# khanh_PB_ip5306_1_0.net
KiCad netlist of a schematic drawn in EAGLE
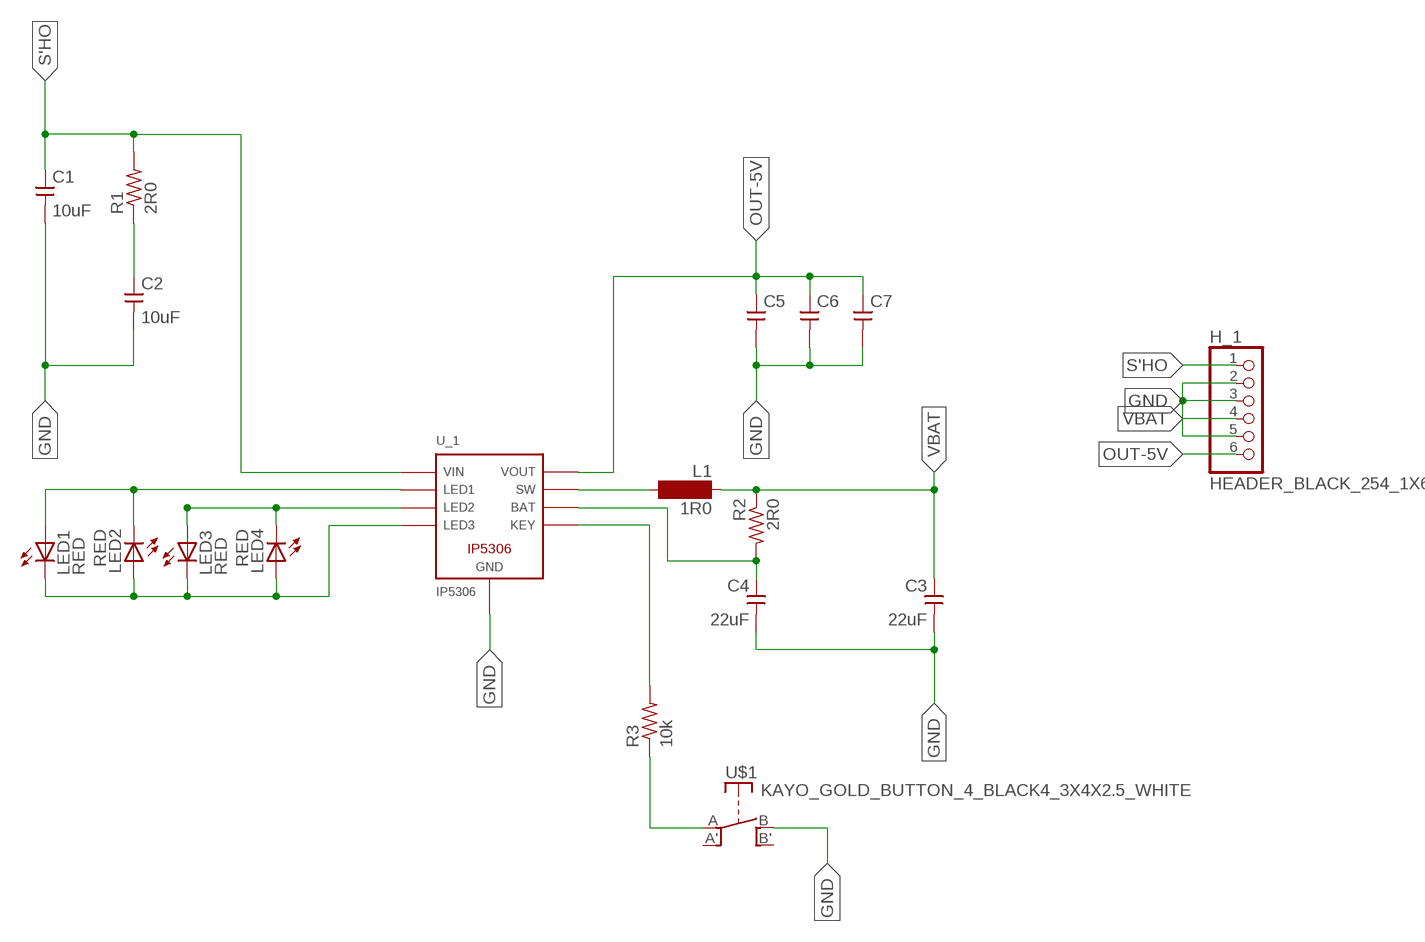
[diagram p0: schematic, sheet 1]

(export (version "E")
  (design (tool "Eeschema 10.0.6"))
  (components
    (comp (ref "C1")
      (value "10uF")
      (footprint "eagle-import:C1206")
      (libsource (lib "eagle-import") (part "KAYO_CAP_CERAMIC_120610UF"))
    )
    (comp (ref "C2")
      (value "10uF")
      (footprint "eagle-import:C1206")
      (libsource (lib "eagle-import") (part "KAYO_CAP_CERAMIC_120610UF"))
    )
    (comp (ref "C3")
      (value "22uF")
      (footprint "eagle-import:C1206")
      (libsource (lib "eagle-import") (part "KAYO_CAP_CERAMIC_120622UF"))
    )
    (comp (ref "C4")
      (value "22uF")
      (footprint "eagle-import:C1206")
      (libsource (lib "eagle-import") (part "KAYO_CAP_CERAMIC_120622UF"))
    )
    (comp (ref "C5")
      (value "KAYO_CAP_CERAMIC22UF_KXN_0603")
      (footprint "eagle-import:KXN_C0603")
      (libsource (lib "eagle-import") (part "KAYO_CAP_CERAMIC_KXN_060322UF"))
    )
    (comp (ref "C6")
      (value "KAYO_CAP_CERAMIC22UF_KXN_0603")
      (footprint "eagle-import:KXN_C0603")
      (libsource (lib "eagle-import") (part "KAYO_CAP_CERAMIC_KXN_060322UF"))
    )
    (comp (ref "C7")
      (value "KAYO_CAP_CERAMIC22UF_KXN_0603")
      (footprint "eagle-import:KXN_C0603")
      (libsource (lib "eagle-import") (part "KAYO_CAP_CERAMIC_KXN_060322UF"))
    )
    (comp (ref "H_1")
      (value "HEADER_BLACK_254_1X6")
      (footprint "eagle-import:HEADER_1X6_254")
      (libsource (lib "eagle-import") (part "KXN_HEADER_1X6"))
    )
    (comp (ref "L1")
      (value "1R0")
      (footprint "eagle-import:CKST_0603_0630_PACK")
      (libsource (lib "eagle-import") (part "INDUCTOR_FEEDER_KAYO_0650"))
    )
    (comp (ref "LED1")
      (value "RED")
      (footprint "eagle-import:KXN_LED_0603")
      (libsource (lib "eagle-import") (part "KAYO_LED_KXN_LED_0603_RED"))
    )
    (comp (ref "LED2")
      (value "RED")
      (footprint "eagle-import:KXN_LED_0603")
      (libsource (lib "eagle-import") (part "KAYO_LED_KXN_LED_0603_RED"))
    )
    (comp (ref "LED3")
      (value "RED")
      (footprint "eagle-import:KXN_LED_0603")
      (libsource (lib "eagle-import") (part "KAYO_LED_KXN_LED_0603_RED"))
    )
    (comp (ref "LED4")
      (value "RED")
      (footprint "eagle-import:KXN_LED_0603")
      (libsource (lib "eagle-import") (part "KAYO_LED_KXN_LED_0603_RED"))
    )
    (comp (ref "R1")
      (value "2R0")
      (footprint "eagle-import:R0603")
      (libsource (lib "eagle-import") (part "R-US_R0603"))
    )
    (comp (ref "R2")
      (value "2R0")
      (footprint "eagle-import:R0603")
      (libsource (lib "eagle-import") (part "R-US_R0603"))
    )
    (comp (ref "R3")
      (value "10k")
      (footprint "eagle-import:R0603")
      (libsource (lib "eagle-import") (part "R-US_R0603"))
    )
    (comp (ref "U$1")
      (value "KAYO_GOLD_BUTTON_4_BLACK4_3X4X2.5_WHITE")
      (footprint "eagle-import:KXN_BUTTON_3_4_2.5MM")
      (libsource (lib "eagle-import") (part "KAYO_GOLD_BUTTON_44_3X4X2.5_WHITE_BLACK"))
    )
    (comp (ref "U_1")
      (value "IP5306")
      (footprint "eagle-import:ESOP8")
      (libsource (lib "eagle-import") (part "IP5306_1"))
    )
  )
  (nets
    (net (code "1") (name "GND") (class "Default")
      (node (ref "C1") (pin "2") (pinfunction "-_2") (pintype "passive"))
      (node (ref "C2") (pin "2") (pinfunction "-_2") (pintype "passive"))
      (node (ref "C3") (pin "2") (pinfunction "-_2") (pintype "passive"))
      (node (ref "C4") (pin "2") (pinfunction "-_2") (pintype "passive"))
      (node (ref "C5") (pin "2") (pinfunction "-_2") (pintype "passive"))
      (node (ref "C6") (pin "2") (pinfunction "-_2") (pintype "passive"))
      (node (ref "C7") (pin "2") (pinfunction "-_2") (pintype "passive"))
      (node (ref "H_1") (pin "2") (pinfunction "2_2") (pintype "passive"))
      (node (ref "H_1") (pin "3") (pinfunction "3_3") (pintype "passive"))
      (node (ref "H_1") (pin "5") (pinfunction "5_5") (pintype "passive"))
      (node (ref "U$1") (pin "B") (pinfunction "B_B") (pintype "passive"))
      (node (ref "U_1") (pin "9") (pinfunction "P$9_9") (pintype "power_in"))
    )
    (net (code "2") (name "Net-(C2-+)") (class "Default")
      (node (ref "C2") (pin "1") (pinfunction "+_1") (pintype "passive"))
      (node (ref "R1") (pin "1") (pinfunction "1_1") (pintype "passive"))
    )
    (net (code "3") (name "Net-(C4-+)") (class "Default")
      (node (ref "C4") (pin "1") (pinfunction "+_1") (pintype "passive"))
      (node (ref "R2") (pin "2") (pinfunction "2_2") (pintype "passive"))
      (node (ref "U_1") (pin "6") (pinfunction "P$6_6") (pintype "bidirectional"))
    )
    (net (code "4") (name "Net-(L1-2)") (class "Default")
      (node (ref "L1") (pin "P$2") (pinfunction "2_P$2") (pintype "passive"))
      (node (ref "U_1") (pin "7") (pinfunction "P$7_7") (pintype "bidirectional"))
    )
    (net (code "5") (name "Net-(R3-Pad1)") (class "Default")
      (node (ref "R3") (pin "1") (pinfunction "1_1") (pintype "passive"))
      (node (ref "U$1") (pin "A") (pinfunction "A_A") (pintype "passive"))
    )
    (net (code "6") (name "Net-(U_1-P$2)") (class "Default")
      (node (ref "LED1") (pin "A") (pinfunction "A_A") (pintype "passive"))
      (node (ref "LED2") (pin "C") (pinfunction "C_C") (pintype "passive"))
      (node (ref "U_1") (pin "2") (pinfunction "P$2_2") (pintype "bidirectional"))
    )
    (net (code "7") (name "Net-(U_1-P$3)") (class "Default")
      (node (ref "LED3") (pin "A") (pinfunction "A_A") (pintype "passive"))
      (node (ref "LED4") (pin "C") (pinfunction "C_C") (pintype "passive"))
      (node (ref "U_1") (pin "3") (pinfunction "P$3_3") (pintype "bidirectional"))
    )
    (net (code "8") (name "Net-(U_1-P$4)") (class "Default")
      (node (ref "LED1") (pin "C") (pinfunction "C_C") (pintype "passive"))
      (node (ref "LED2") (pin "A") (pinfunction "A_A") (pintype "passive"))
      (node (ref "LED3") (pin "C") (pinfunction "C_C") (pintype "passive"))
      (node (ref "LED4") (pin "A") (pinfunction "A_A") (pintype "passive"))
      (node (ref "U_1") (pin "4") (pinfunction "P$4_4") (pintype "bidirectional"))
    )
    (net (code "9") (name "Net-(U_1-P$5)") (class "Default")
      (node (ref "R3") (pin "2") (pinfunction "2_2") (pintype "passive"))
      (node (ref "U_1") (pin "5") (pinfunction "P$5_5") (pintype "bidirectional"))
    )
    (net (code "10") (name "OUT-5V") (class "Default")
      (node (ref "C5") (pin "1") (pinfunction "+_1") (pintype "passive"))
      (node (ref "C6") (pin "1") (pinfunction "+_1") (pintype "passive"))
      (node (ref "C7") (pin "1") (pinfunction "+_1") (pintype "passive"))
      (node (ref "H_1") (pin "6") (pinfunction "6_6") (pintype "passive"))
      (node (ref "U_1") (pin "8") (pinfunction "P$8_8") (pintype "power_in"))
    )
    (net (code "11") (name "S'HO") (class "Default")
      (node (ref "C1") (pin "1") (pinfunction "+_1") (pintype "passive"))
      (node (ref "H_1") (pin "1") (pinfunction "1_1") (pintype "passive"))
      (node (ref "R1") (pin "2") (pinfunction "2_2") (pintype "passive"))
      (node (ref "U_1") (pin "1") (pinfunction "P$1_1") (pintype "power_in"))
    )
    (net (code "12") (name "VBAT") (class "Default")
      (node (ref "C3") (pin "1") (pinfunction "+_1") (pintype "passive"))
      (node (ref "H_1") (pin "4") (pinfunction "4_4") (pintype "passive"))
      (node (ref "L1") (pin "P$1") (pinfunction "1_P$1") (pintype "passive"))
      (node (ref "R2") (pin "1") (pinfunction "1_1") (pintype "passive"))
    )
    (net (code "13") (name "unconnected-(U$1-PadA')") (class "Default")
      (node (ref "U$1") (pin "A'") (pinfunction "A'_A'") (pintype "passive"))
    )
    (net (code "14") (name "unconnected-(U$1-PadB')") (class "Default")
      (node (ref "U$1") (pin "B'") (pinfunction "B'_B'") (pintype "passive"))
    )
  )
)
